# led.net
KiCad netlist of a schematic drawn in EAGLE
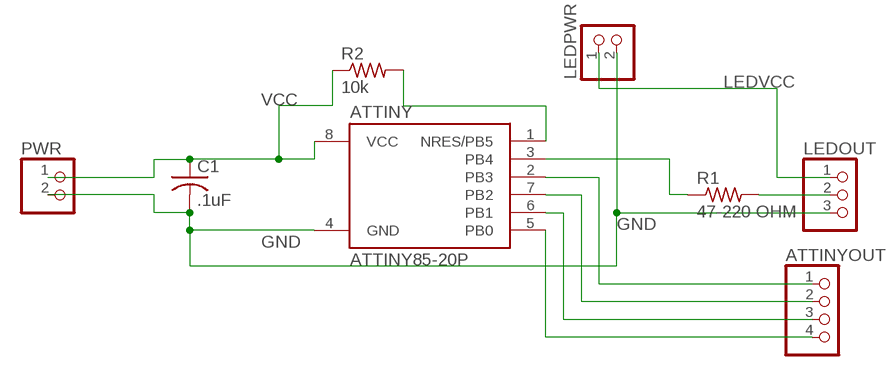
[diagram p0: schematic, sheet 1]

(export (version "E")
  (design (tool "Eeschema 10.0.6"))
  (components
    (comp (ref "ATTINY")
      (value "ATTINY85-20P")
      (footprint "eagle-import:PDIP08_300MIL")
      (libsource (lib "eagle-import") (part "ATTINY85P-20"))
    )
    (comp (ref "ATTINYOUT")
      (value "PINHD-1X4")
      (footprint "eagle-import:1X04")
      (libsource (lib "eagle-import") (part "PINHD-1X4"))
    )
    (comp (ref "C1")
      (value ".1uF")
      (footprint "eagle-import:C050-025X075")
      (libsource (lib "eagle-import") (part "C-US050-025X075"))
    )
    (comp (ref "LEDOUT")
      (value "PINHD-1X3")
      (footprint "eagle-import:1X03")
      (libsource (lib "eagle-import") (part "PINHD-1X3"))
    )
    (comp (ref "LEDPWR")
      (value "PINHD-1X2")
      (footprint "eagle-import:1X02")
      (libsource (lib "eagle-import") (part "PINHD-1X2"))
    )
    (comp (ref "PWR")
      (value "PINHD-1X2")
      (footprint "eagle-import:1X02")
      (libsource (lib "eagle-import") (part "PINHD-1X2"))
    )
    (comp (ref "R1")
      (value "47-220 OHM")
      (footprint "eagle-import:0207_12")
      (libsource (lib "eagle-import") (part "R-US_0207/12"))
    )
    (comp (ref "R2")
      (value "10k")
      (footprint "eagle-import:0207_12")
      (libsource (lib "eagle-import") (part "R-US_0207/12"))
    )
  )
  (nets
    (net (code "1") (name "/GND") (class "Default")
      (node (ref "ATTINY") (pin "4") (pinfunction "GND_4") (pintype "power_in"))
      (node (ref "C1") (pin "2") (pinfunction "2_2") (pintype "passive"))
      (node (ref "LEDOUT") (pin "3") (pinfunction "3_3") (pintype "passive"))
      (node (ref "LEDPWR") (pin "2") (pinfunction "2_2") (pintype "passive"))
      (node (ref "PWR") (pin "2") (pinfunction "2_2") (pintype "passive"))
    )
    (net (code "2") (name "/LEDVCC") (class "Default")
      (node (ref "LEDOUT") (pin "1") (pinfunction "1_1") (pintype "passive"))
      (node (ref "LEDPWR") (pin "1") (pinfunction "1_1") (pintype "passive"))
    )
    (net (code "3") (name "/VCC") (class "Default")
      (node (ref "ATTINY") (pin "8") (pinfunction "VCC_8") (pintype "power_in"))
      (node (ref "C1") (pin "1") (pinfunction "1_1") (pintype "passive"))
      (node (ref "PWR") (pin "1") (pinfunction "1_1") (pintype "passive"))
      (node (ref "R2") (pin "1") (pinfunction "1_1") (pintype "passive"))
    )
    (net (code "4") (name "Net-(ATTINY-NRES{slash}PB5)") (class "Default")
      (node (ref "ATTINY") (pin "1") (pinfunction "NRES/PB5_1") (pintype "bidirectional"))
      (node (ref "R2") (pin "2") (pinfunction "2_2") (pintype "passive"))
    )
    (net (code "5") (name "Net-(ATTINY-PB0)") (class "Default")
      (node (ref "ATTINY") (pin "5") (pinfunction "PB0_5") (pintype "bidirectional"))
      (node (ref "ATTINYOUT") (pin "4") (pinfunction "4_4") (pintype "passive"))
    )
    (net (code "6") (name "Net-(ATTINY-PB1)") (class "Default")
      (node (ref "ATTINY") (pin "6") (pinfunction "PB1_6") (pintype "bidirectional"))
      (node (ref "ATTINYOUT") (pin "3") (pinfunction "3_3") (pintype "passive"))
    )
    (net (code "7") (name "Net-(ATTINY-PB2)") (class "Default")
      (node (ref "ATTINY") (pin "7") (pinfunction "PB2_7") (pintype "bidirectional"))
      (node (ref "ATTINYOUT") (pin "2") (pinfunction "2_2") (pintype "passive"))
    )
    (net (code "8") (name "Net-(ATTINY-PB3)") (class "Default")
      (node (ref "ATTINY") (pin "2") (pinfunction "PB3_2") (pintype "bidirectional"))
      (node (ref "ATTINYOUT") (pin "1") (pinfunction "1_1") (pintype "passive"))
    )
    (net (code "9") (name "Net-(ATTINY-PB4)") (class "Default")
      (node (ref "ATTINY") (pin "3") (pinfunction "PB4_3") (pintype "bidirectional"))
      (node (ref "R1") (pin "1") (pinfunction "1_1") (pintype "passive"))
    )
    (net (code "10") (name "Net-(LEDOUT-Pad2)") (class "Default")
      (node (ref "LEDOUT") (pin "2") (pinfunction "2_2") (pintype "passive"))
      (node (ref "R1") (pin "2") (pinfunction "2_2") (pintype "passive"))
    )
  )
)
